# LCDTFT_RTP_DRV_STMPE811.net
KiCad netlist of a schematic drawn in Altium Designer
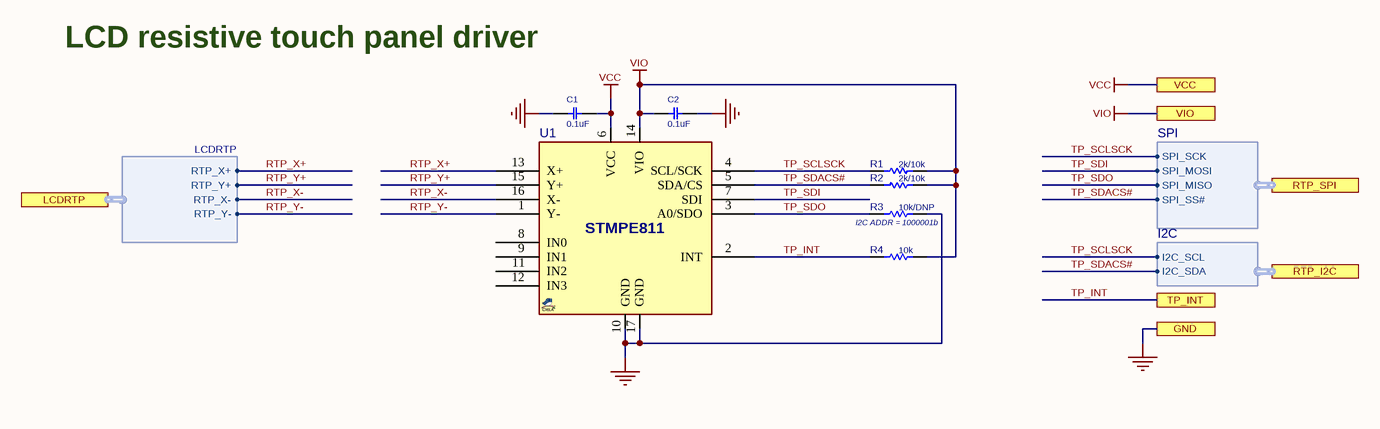
[diagram p0: LCDTFT_RTP_DRV_STMPE811.SchDoc]

(export (version "E")
  (design (tool "Eeschema 10.0.6"))
  (components
    (comp (ref "C1")
      (value "0.1uF")
      (footprint "C0402")
      (description "CAP, MLCC")
      (fields (field (name "MANF_P#") "GRM155R71H104KE14D") (field (name "MANF") "Murata"))
      (libsource (lib "passive_smd") (part "CAP_SMD_MLCC"))
    )
    (comp (ref "C2")
      (value "0.1uF")
      (footprint "C0402")
      (description "CAP, MLCC")
      (fields (field (name "MANF_P#") "GRM155R71H104KE14D") (field (name "MANF") "Murata"))
      (libsource (lib "passive_smd") (part "CAP_SMD_MLCC"))
    )
    (comp (ref "R1")
      (value "2k/10k")
      (footprint "R0402")
      (description "RESISTOR, SMD")
      (libsource (lib "passive_res_smd") (part "RES_SMD"))
    )
    (comp (ref "R2")
      (value "2k/10k")
      (footprint "R0402")
      (description "RESISTOR, SMD")
      (libsource (lib "passive_res_smd") (part "RES_SMD"))
    )
    (comp (ref "R3")
      (value "10k/DNP")
      (footprint "R0402")
      (description "RESISTOR, SMD")
      (libsource (lib "passive_res_smd") (part "RES_SMD"))
    )
    (comp (ref "R4")
      (value "10k")
      (footprint "R0402")
      (description "RESISTOR, SMD")
      (libsource (lib "passive_res_smd") (part "RES_SMD"))
    )
    (comp (ref "U1")
      (value "STMPE811")
      (footprint "QFN50_16T_3X3")
      (description "LCD resistive touch panel driver")
      (fields (field (name "MANF") "ST") (field (name "MANF_P#") "STMPE811Q"))
      (libsource (lib "lcd_resistive_touch_driver") (part "STMPE811_QFN16"))
    )
  )
  (nets
    (net (code "4") (name "/RTP_X+") (class "Default")
      (node (ref "U1") (pin "13") (pinfunction "X+_13") (pintype "passive"))
    )
    (net (code "5") (name "/RTP_X-") (class "Default")
      (node (ref "U1") (pin "16") (pinfunction "X-_16") (pintype "passive"))
    )
    (net (code "6") (name "/RTP_Y+") (class "Default")
      (node (ref "U1") (pin "15") (pinfunction "Y+_15") (pintype "passive"))
    )
    (net (code "7") (name "/RTP_Y-") (class "Default")
      (node (ref "U1") (pin "1") (pinfunction "Y-_1") (pintype "passive"))
    )
    (net (code "8") (name "/TP_INT") (class "Default")
      (node (ref "R4") (pin "2") (pinfunction "2_2") (pintype "passive"))
      (node (ref "U1") (pin "2") (pinfunction "INT_2") (pintype "passive"))
    )
    (net (code "9") (name "/TP_SCLSCK") (class "Default")
      (node (ref "R1") (pin "2") (pinfunction "2_2") (pintype "passive"))
      (node (ref "U1") (pin "4") (pinfunction "SCL/SCK_4") (pintype "passive"))
    )
    (net (code "10") (name "/TP_SDACS#") (class "Default")
      (node (ref "R2") (pin "2") (pinfunction "2_2") (pintype "passive"))
      (node (ref "U1") (pin "5") (pinfunction "SDA/CS_5") (pintype "passive"))
    )
    (net (code "11") (name "/TP_SDI") (class "Default")
      (node (ref "U1") (pin "7") (pinfunction "SDI_7") (pintype "passive"))
    )
    (net (code "12") (name "/TP_SDO") (class "Default")
      (node (ref "R3") (pin "2") (pinfunction "2_2") (pintype "passive"))
      (node (ref "U1") (pin "3") (pinfunction "A0/SDO_3") (pintype "passive"))
    )
    (net (code "16") (name "GND") (class "Default")
      (node (ref "C1") (pin "1") (pinfunction "1_1") (pintype "passive"))
      (node (ref "C2") (pin "1") (pinfunction "1_1") (pintype "passive"))
      (node (ref "R3") (pin "1") (pinfunction "1_1") (pintype "passive"))
      (node (ref "U1") (pin "10") (pinfunction "GND_10") (pintype "passive"))
      (node (ref "U1") (pin "17") (pinfunction "GND_17") (pintype "passive"))
    )
    (net (code "17") (name "VCC") (class "Default")
      (node (ref "C1") (pin "2") (pinfunction "2_2") (pintype "passive"))
      (node (ref "U1") (pin "6") (pinfunction "VCC_6") (pintype "passive"))
    )
    (net (code "18") (name "VIO") (class "Default")
      (node (ref "C2") (pin "2") (pinfunction "2_2") (pintype "passive"))
      (node (ref "R1") (pin "1") (pinfunction "1_1") (pintype "passive"))
      (node (ref "R2") (pin "1") (pinfunction "1_1") (pintype "passive"))
      (node (ref "R4") (pin "1") (pinfunction "1_1") (pintype "passive"))
      (node (ref "U1") (pin "14") (pinfunction "VIO_14") (pintype "passive"))
    )
    (net (code "19") (name "unconnected-(U1-IN0-Pad8)") (class "Default")
      (node (ref "U1") (pin "8") (pinfunction "IN0_8") (pintype "passive"))
    )
    (net (code "20") (name "unconnected-(U1-IN1-Pad9)") (class "Default")
      (node (ref "U1") (pin "9") (pinfunction "IN1_9") (pintype "passive"))
    )
    (net (code "21") (name "unconnected-(U1-IN2-Pad11)") (class "Default")
      (node (ref "U1") (pin "11") (pinfunction "IN2_11") (pintype "passive"))
    )
    (net (code "22") (name "unconnected-(U1-IN3-Pad12)") (class "Default")
      (node (ref "U1") (pin "12") (pinfunction "IN3_12") (pintype "passive"))
    )
  )
)
